# power.net
KiCad netlist of a schematic drawn in Altium Designer
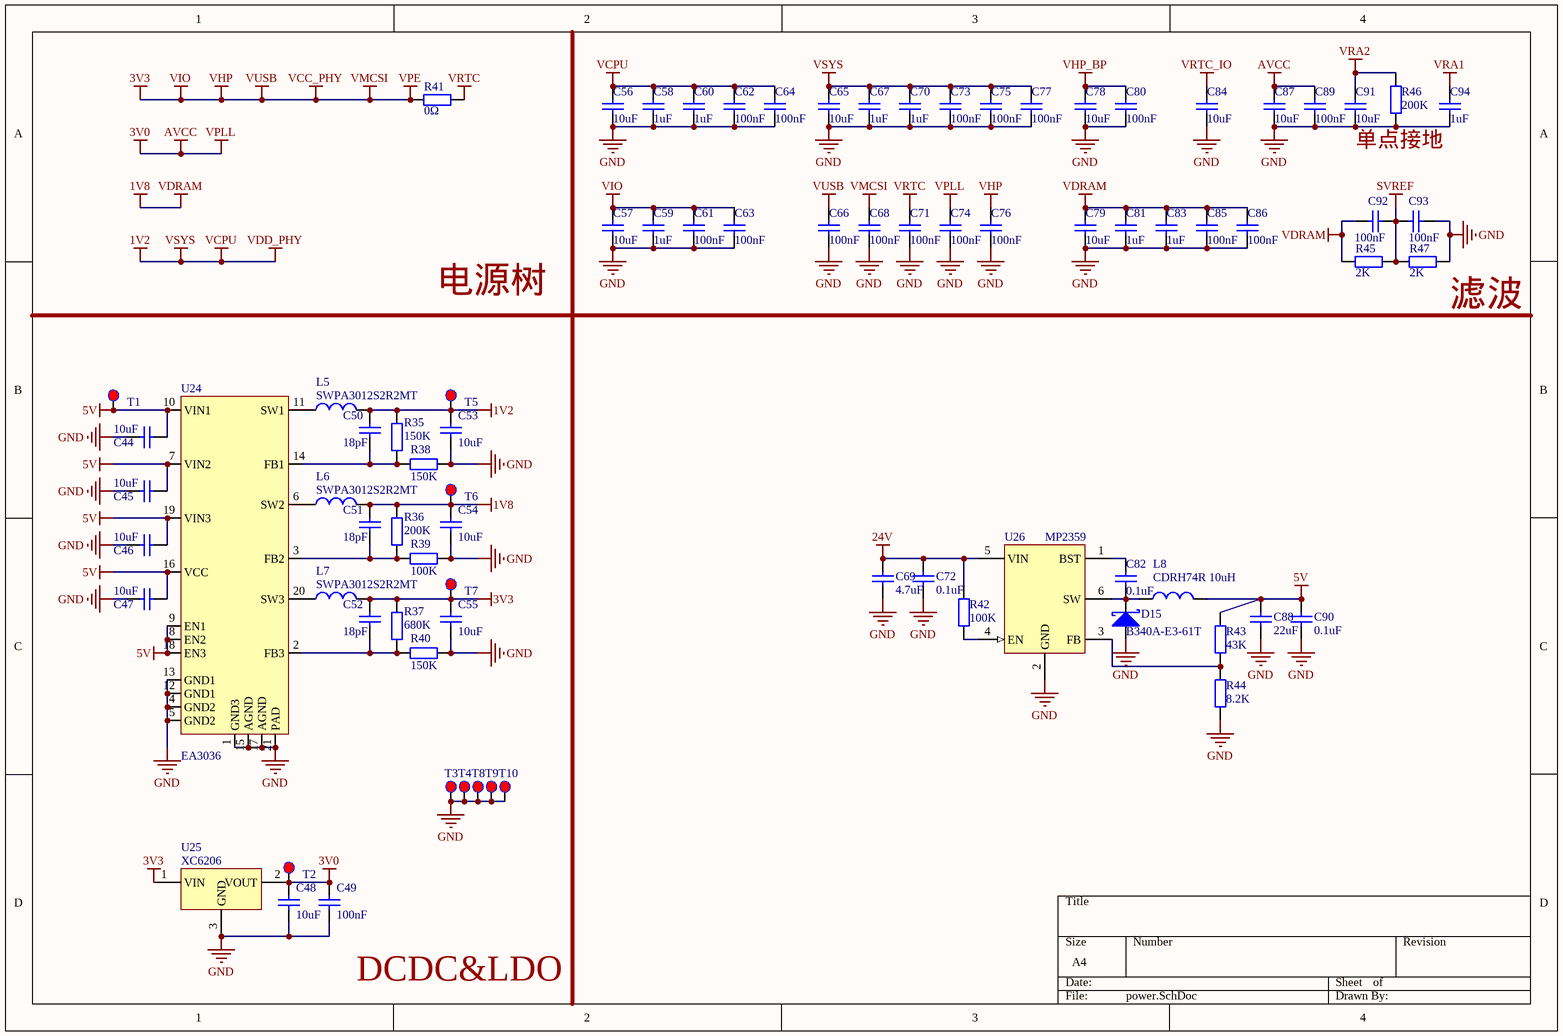
[diagram p0: power.SchDoc]

(export (version "E")
  (design (tool "Eeschema 10.0.6"))
  (components
    (comp (ref "C44")
      (value "10uF")
      (footprint "CAPC1608L")
      (description "Capacitor")
      (fields (field (name "PUBLISHER") "Altium Limited"))
      (libsource (lib "Peace的集成库") (part "Cap1"))
    )
    (comp (ref "C45")
      (value "10uF")
      (footprint "CAPC1608L")
      (description "Capacitor")
      (fields (field (name "PUBLISHER") "Altium Limited"))
      (libsource (lib "Peace的集成库") (part "Cap1"))
    )
    (comp (ref "C46")
      (value "10uF")
      (footprint "CAPC1608L")
      (description "Capacitor")
      (fields (field (name "PUBLISHER") "Altium Limited"))
      (libsource (lib "Peace的集成库") (part "Cap1"))
    )
    (comp (ref "C47")
      (value "10uF")
      (footprint "CAPC1608L")
      (description "Capacitor")
      (fields (field (name "PUBLISHER") "Altium Limited"))
      (libsource (lib "Peace的集成库") (part "Cap1"))
    )
    (comp (ref "C48")
      (value "10uF")
      (footprint "CAPC1608L")
      (description "Capacitor")
      (fields (field (name "PUBLISHER") "Altium Limited"))
      (libsource (lib "Peace的集成库") (part "Cap1"))
    )
    (comp (ref "C49")
      (value "100nF")
      (footprint "CAPC1608L")
      (description "Capacitor")
      (fields (field (name "PUBLISHER") "Altium Limited"))
      (libsource (lib "Peace的集成库") (part "Cap1"))
    )
    (comp (ref "C50")
      (value "18pF")
      (footprint "CAPC1608L")
      (description "Capacitor")
      (fields (field (name "PUBLISHER") "Altium Limited"))
      (libsource (lib "Peace的集成库") (part "Cap1"))
    )
    (comp (ref "C51")
      (value "18pF")
      (footprint "CAPC1608L")
      (description "Capacitor")
      (fields (field (name "PUBLISHER") "Altium Limited"))
      (libsource (lib "Peace的集成库") (part "Cap1"))
    )
    (comp (ref "C52")
      (value "18pF")
      (footprint "CAPC1608L")
      (description "Capacitor")
      (fields (field (name "PUBLISHER") "Altium Limited"))
      (libsource (lib "Peace的集成库") (part "Cap1"))
    )
    (comp (ref "C53")
      (value "10uF")
      (footprint "CAPC1608L")
      (description "Capacitor")
      (fields (field (name "PUBLISHER") "Altium Limited"))
      (libsource (lib "Peace的集成库") (part "Cap1"))
    )
    (comp (ref "C54")
      (value "10uF")
      (footprint "CAPC1608L")
      (description "Capacitor")
      (fields (field (name "PUBLISHER") "Altium Limited"))
      (libsource (lib "Peace的集成库") (part "Cap1"))
    )
    (comp (ref "C55")
      (value "10uF")
      (footprint "CAPC1608L")
      (description "Capacitor")
      (fields (field (name "PUBLISHER") "Altium Limited"))
      (libsource (lib "Peace的集成库") (part "Cap1"))
    )
    (comp (ref "C56")
      (value "10uF")
      (footprint "CAPC1608L")
      (description "Capacitor")
      (fields (field (name "PUBLISHER") "Altium Limited"))
      (libsource (lib "Peace的集成库") (part "Cap1"))
    )
    (comp (ref "C57")
      (value "10uF")
      (footprint "CAPC1608L")
      (description "Capacitor")
      (fields (field (name "PUBLISHER") "Altium Limited"))
      (libsource (lib "Peace的集成库") (part "Cap1"))
    )
    (comp (ref "C58")
      (value "1uF")
      (footprint "CAPC1608L")
      (description "Capacitor")
      (fields (field (name "PUBLISHER") "Altium Limited"))
      (libsource (lib "Peace的集成库") (part "Cap1"))
    )
    (comp (ref "C59")
      (value "1uF")
      (footprint "CAPC1608L")
      (description "Capacitor")
      (fields (field (name "PUBLISHER") "Altium Limited"))
      (libsource (lib "Peace的集成库") (part "Cap1"))
    )
    (comp (ref "C60")
      (value "1uF")
      (footprint "CAPC1608L")
      (description "Capacitor")
      (fields (field (name "PUBLISHER") "Altium Limited"))
      (libsource (lib "Peace的集成库") (part "Cap1"))
    )
    (comp (ref "C61")
      (value "100nF")
      (footprint "CAPC1608L")
      (description "Capacitor")
      (fields (field (name "PUBLISHER") "Altium Limited"))
      (libsource (lib "Peace的集成库") (part "Cap1"))
    )
    (comp (ref "C62")
      (value "100nF")
      (footprint "CAPC1608L")
      (description "Capacitor")
      (fields (field (name "PUBLISHER") "Altium Limited"))
      (libsource (lib "Peace的集成库") (part "Cap1"))
    )
    (comp (ref "C63")
      (value "100nF")
      (footprint "CAPC1608L")
      (description "Capacitor")
      (fields (field (name "PUBLISHER") "Altium Limited"))
      (libsource (lib "Peace的集成库") (part "Cap1"))
    )
    (comp (ref "C64")
      (value "100nF")
      (footprint "CAPC1608L")
      (description "Capacitor")
      (fields (field (name "PUBLISHER") "Altium Limited"))
      (libsource (lib "Peace的集成库") (part "Cap1"))
    )
    (comp (ref "C65")
      (value "10uF")
      (footprint "CAPC1608L")
      (description "Capacitor")
      (fields (field (name "PUBLISHER") "Altium Limited"))
      (libsource (lib "Peace的集成库") (part "Cap1"))
    )
    (comp (ref "C66")
      (value "100nF")
      (footprint "CAPC1608L")
      (description "Capacitor")
      (fields (field (name "PUBLISHER") "Altium Limited"))
      (libsource (lib "Peace的集成库") (part "Cap1"))
    )
    (comp (ref "C67")
      (value "1uF")
      (footprint "CAPC1608L")
      (description "Capacitor")
      (fields (field (name "PUBLISHER") "Altium Limited"))
      (libsource (lib "Peace的集成库") (part "Cap1"))
    )
    (comp (ref "C68")
      (value "100nF")
      (footprint "CAPC1608L")
      (description "Capacitor")
      (fields (field (name "PUBLISHER") "Altium Limited"))
      (libsource (lib "Peace的集成库") (part "Cap1"))
    )
    (comp (ref "C69")
      (value "4.7uF")
      (footprint "CAPC3216L")
      (description "Capacitor")
      (fields (field (name "PUBLISHER") "Altium Limited"))
      (libsource (lib "Peace的集成库") (part "Cap1"))
    )
    (comp (ref "C70")
      (value "1uF")
      (footprint "CAPC1608L")
      (description "Capacitor")
      (fields (field (name "PUBLISHER") "Altium Limited"))
      (libsource (lib "Peace的集成库") (part "Cap1"))
    )
    (comp (ref "C71")
      (value "100nF")
      (footprint "CAPC1608L")
      (description "Capacitor")
      (fields (field (name "PUBLISHER") "Altium Limited"))
      (libsource (lib "Peace的集成库") (part "Cap1"))
    )
    (comp (ref "C72")
      (value "0.1uF")
      (footprint "CAPC2012L")
      (description "Capacitor")
      (fields (field (name "PUBLISHER") "Altium Limited"))
      (libsource (lib "Peace的集成库") (part "Cap1"))
    )
    (comp (ref "C73")
      (value "100nF")
      (footprint "CAPC1608L")
      (description "Capacitor")
      (fields (field (name "PUBLISHER") "Altium Limited"))
      (libsource (lib "Peace的集成库") (part "Cap1"))
    )
    (comp (ref "C74")
      (value "100nF")
      (footprint "CAPC1608L")
      (description "Capacitor")
      (fields (field (name "PUBLISHER") "Altium Limited"))
      (libsource (lib "Peace的集成库") (part "Cap1"))
    )
    (comp (ref "C75")
      (value "100nF")
      (footprint "CAPC1608L")
      (description "Capacitor")
      (fields (field (name "PUBLISHER") "Altium Limited"))
      (libsource (lib "Peace的集成库") (part "Cap1"))
    )
    (comp (ref "C76")
      (value "100nF")
      (footprint "CAPC1608L")
      (description "Capacitor")
      (fields (field (name "PUBLISHER") "Altium Limited"))
      (libsource (lib "Peace的集成库") (part "Cap1"))
    )
    (comp (ref "C77")
      (value "100nF")
      (footprint "CAPC1608L")
      (description "Capacitor")
      (fields (field (name "PUBLISHER") "Altium Limited"))
      (libsource (lib "Peace的集成库") (part "Cap1"))
    )
    (comp (ref "C78")
      (value "10uF")
      (footprint "CAPC1608L")
      (description "Capacitor")
      (fields (field (name "PUBLISHER") "Altium Limited"))
      (libsource (lib "Peace的集成库") (part "Cap1"))
    )
    (comp (ref "C79")
      (value "10uF")
      (footprint "CAPC1608L")
      (description "Capacitor")
      (fields (field (name "PUBLISHER") "Altium Limited"))
      (libsource (lib "Peace的集成库") (part "Cap1"))
    )
    (comp (ref "C80")
      (value "100nF")
      (footprint "CAPC1608L")
      (description "Capacitor")
      (fields (field (name "PUBLISHER") "Altium Limited"))
      (libsource (lib "Peace的集成库") (part "Cap1"))
    )
    (comp (ref "C81")
      (value "1uF")
      (footprint "CAPC1608L")
      (description "Capacitor")
      (fields (field (name "PUBLISHER") "Altium Limited"))
      (libsource (lib "Peace的集成库") (part "Cap1"))
    )
    (comp (ref "C82")
      (value "0.1uF")
      (footprint "CAPC1608L")
      (description "Capacitor")
      (fields (field (name "PUBLISHER") "Altium Limited"))
      (libsource (lib "Peace的集成库") (part "Cap1"))
    )
    (comp (ref "C83")
      (value "1uF")
      (footprint "CAPC1608L")
      (description "Capacitor")
      (fields (field (name "PUBLISHER") "Altium Limited"))
      (libsource (lib "Peace的集成库") (part "Cap1"))
    )
    (comp (ref "C84")
      (value "10uF")
      (footprint "CAPC1608L")
      (description "Capacitor")
      (fields (field (name "PUBLISHER") "Altium Limited"))
      (libsource (lib "Peace的集成库") (part "Cap1"))
    )
    (comp (ref "C85")
      (value "100nF")
      (footprint "CAPC1608L")
      (description "Capacitor")
      (fields (field (name "PUBLISHER") "Altium Limited"))
      (libsource (lib "Peace的集成库") (part "Cap1"))
    )
    (comp (ref "C86")
      (value "100nF")
      (footprint "CAPC1608L")
      (description "Capacitor")
      (fields (field (name "PUBLISHER") "Altium Limited"))
      (libsource (lib "Peace的集成库") (part "Cap1"))
    )
    (comp (ref "C87")
      (value "10uF")
      (footprint "CAPC1608L")
      (description "Capacitor")
      (fields (field (name "PUBLISHER") "Altium Limited"))
      (libsource (lib "Peace的集成库") (part "Cap1"))
    )
    (comp (ref "C88")
      (value "22uF")
      (footprint "CAPC3216L")
      (description "Capacitor")
      (fields (field (name "PUBLISHER") "Altium Limited"))
      (libsource (lib "Peace的集成库") (part "Cap1"))
    )
    (comp (ref "C89")
      (value "100nF")
      (footprint "CAPC1608L")
      (description "Capacitor")
      (fields (field (name "PUBLISHER") "Altium Limited"))
      (libsource (lib "Peace的集成库") (part "Cap1"))
    )
    (comp (ref "C90")
      (value "0.1uF")
      (footprint "CAPC2012L")
      (description "Capacitor")
      (fields (field (name "PUBLISHER") "Altium Limited"))
      (libsource (lib "Peace的集成库") (part "Cap1"))
    )
    (comp (ref "C91")
      (value "10uF")
      (footprint "CAPC1608L")
      (description "Capacitor")
      (fields (field (name "PUBLISHER") "Altium Limited"))
      (libsource (lib "Peace的集成库") (part "Cap1"))
    )
    (comp (ref "C92")
      (value "100nF")
      (footprint "CAPC1608L")
      (description "Capacitor")
      (fields (field (name "PUBLISHER") "Altium Limited"))
      (libsource (lib "Peace的集成库") (part "Cap1"))
    )
    (comp (ref "C93")
      (value "100nF")
      (footprint "CAPC1608L")
      (description "Capacitor")
      (fields (field (name "PUBLISHER") "Altium Limited"))
      (libsource (lib "Peace的集成库") (part "Cap1"))
    )
    (comp (ref "C94")
      (value "1uF")
      (footprint "CAPC1608L")
      (description "Capacitor")
      (fields (field (name "PUBLISHER") "Altium Limited"))
      (libsource (lib "Peace的集成库") (part "Cap1"))
    )
    (comp (ref "D15")
      (value "B340A-E3-61T")
      (footprint "DO-214AC")
      (description "Schottky Diode")
      (fields (field (name "PUBLISHER") "Altium Limited"))
      (libsource (lib "原理图库") (part "D Schottky"))
    )
    (comp (ref "L5")
      (value "SWPA3012S2R2MT")
      (footprint "IND3012_L")
      (description "Inductor")
      (fields (field (name "PUBLISHER") "Altium Limited"))
      (libsource (lib "Peace的集成库") (part "Inductor"))
    )
    (comp (ref "L6")
      (value "SWPA3012S2R2MT")
      (footprint "IND3012_L")
      (description "Inductor")
      (fields (field (name "PUBLISHER") "Altium Limited"))
      (libsource (lib "Peace的集成库") (part "Inductor"))
    )
    (comp (ref "L7")
      (value "SWPA3012S2R2MT")
      (footprint "IND3012_L")
      (description "Inductor")
      (fields (field (name "PUBLISHER") "Altium Limited"))
      (libsource (lib "Peace的集成库") (part "Inductor"))
    )
    (comp (ref "L8")
      (value "CDRH74R 10uH")
      (footprint "IND_7545")
      (description "Inductor")
      (fields (field (name "PUBLISHER") "Altium Limited"))
      (libsource (lib "原理图库") (part "Inductor"))
    )
    (comp (ref "R35")
      (value "150K")
      (footprint "RESC1608L")
      (description "Resistor")
      (fields (field (name "PUBLISHER") "Altium Limited"))
      (libsource (lib "Peace的集成库") (part "Res1"))
    )
    (comp (ref "R36")
      (value "200K")
      (footprint "RESC1608L")
      (description "Resistor")
      (fields (field (name "PUBLISHER") "Altium Limited"))
      (libsource (lib "Peace的集成库") (part "Res1"))
    )
    (comp (ref "R37")
      (value "680K")
      (footprint "RESC1608L")
      (description "Resistor")
      (fields (field (name "PUBLISHER") "Altium Limited"))
      (libsource (lib "Peace的集成库") (part "Res1"))
    )
    (comp (ref "R38")
      (value "150K")
      (footprint "RESC1608L")
      (description "Resistor")
      (fields (field (name "PUBLISHER") "Altium Limited"))
      (libsource (lib "") (part "Res1_1"))
    )
    (comp (ref "R39")
      (value "100K")
      (footprint "RESC1608L")
      (description "Resistor")
      (fields (field (name "PUBLISHER") "Altium Limited"))
      (libsource (lib "") (part "Res1_1"))
    )
    (comp (ref "R40")
      (value "150K")
      (footprint "RESC1608L")
      (description "Resistor")
      (fields (field (name "PUBLISHER") "Altium Limited"))
      (libsource (lib "") (part "Res1_1"))
    )
    (comp (ref "R41")
      (value "0Ω")
      (footprint "RESC1608L")
      (description "Resistor")
      (fields (field (name "PUBLISHER") "Altium Limited"))
      (libsource (lib "") (part "Res1_2"))
    )
    (comp (ref "R42")
      (value "100K")
      (footprint "RESC1608L")
      (description "Resistor")
      (fields (field (name "PUBLISHER") "Altium Limited"))
      (libsource (lib "Peace的集成库") (part "Res1"))
    )
    (comp (ref "R43")
      (value "43K")
      (footprint "RESC1608L")
      (description "Resistor")
      (fields (field (name "PUBLISHER") "Altium Limited"))
      (libsource (lib "Peace的集成库") (part "Res1"))
    )
    (comp (ref "R44")
      (value "8.2K")
      (footprint "RESC1608L")
      (description "Resistor")
      (fields (field (name "PUBLISHER") "Altium Limited"))
      (libsource (lib "Peace的集成库") (part "Res1"))
    )
    (comp (ref "R45")
      (value "2K")
      (footprint "RESC1608L")
      (description "Resistor")
      (fields (field (name "PUBLISHER") "Altium Limited"))
      (libsource (lib "") (part "Res1_2"))
    )
    (comp (ref "R46")
      (value "200K")
      (footprint "RESC1608L")
      (description "Resistor")
      (fields (field (name "PUBLISHER") "Altium Limited"))
      (libsource (lib "Peace的集成库") (part "Res1"))
    )
    (comp (ref "R47")
      (value "2K")
      (footprint "RESC1608L")
      (description "Resistor")
      (fields (field (name "PUBLISHER") "Altium Limited"))
      (libsource (lib "") (part "Res1_2"))
    )
    (comp (ref "T1")
      (value "TEST_POINT")
      (footprint "TEST_POINT_0.8")
      (description "测试点")
      (libsource (lib "Peace的集成库") (part "TEST_POINT"))
    )
    (comp (ref "T2")
      (value "TEST_POINT")
      (footprint "TEST_POINT_0.8")
      (description "测试点")
      (libsource (lib "Peace的集成库") (part "TEST_POINT"))
    )
    (comp (ref "T3")
      (value "TEST_POINT")
      (footprint "TEST_POINT_0.8")
      (description "测试点")
      (libsource (lib "Peace的集成库") (part "TEST_POINT"))
    )
    (comp (ref "T4")
      (value "TEST_POINT")
      (footprint "TEST_POINT_0.8")
      (description "测试点")
      (libsource (lib "Peace的集成库") (part "TEST_POINT"))
    )
    (comp (ref "T5")
      (value "TEST_POINT")
      (footprint "TEST_POINT_0.8")
      (description "测试点")
      (libsource (lib "Peace的集成库") (part "TEST_POINT"))
    )
    (comp (ref "T6")
      (value "TEST_POINT")
      (footprint "TEST_POINT_0.8")
      (description "测试点")
      (libsource (lib "Peace的集成库") (part "TEST_POINT"))
    )
    (comp (ref "T7")
      (value "TEST_POINT")
      (footprint "TEST_POINT_0.8")
      (description "测试点")
      (libsource (lib "Peace的集成库") (part "TEST_POINT"))
    )
    (comp (ref "T8")
      (value "TEST_POINT")
      (footprint "TEST_POINT_0.8")
      (description "测试点")
      (libsource (lib "Peace的集成库") (part "TEST_POINT"))
    )
    (comp (ref "T9")
      (value "TEST_POINT")
      (footprint "TEST_POINT_0.8")
      (description "测试点")
      (libsource (lib "Peace的集成库") (part "TEST_POINT"))
    )
    (comp (ref "T10")
      (value "TEST_POINT")
      (footprint "TEST_POINT_0.8")
      (description "测试点")
      (libsource (lib "Peace的集成库") (part "TEST_POINT"))
    )
    (comp (ref "U24") (value "EA3036") (footprint "QFN20_L") (libsource (lib "原理图库") (part "EA3036")))
    (comp (ref "U25")
      (value "XC6206")
      (footprint "SOT23_L")
      (libsource (lib "Peace的集成库") (part "LDO-SOT23-3"))
    )
    (comp (ref "U26")
      (value "MP2359")
      (footprint "SOT23-6_L")
      (description "1.2A, 24V, 1.4MHz异步降压转换器")
      (libsource (lib "Peace的集成库") (part "MP2359"))
    )
  )
  (nets
    (net (code "1") (name "1V2") (class "Default")
      (node (ref "C50") (pin "2") (pinfunction "2_2") (pintype "passive"))
      (node (ref "C53") (pin "2") (pinfunction "2_2") (pintype "passive"))
      (node (ref "C56") (pin "2") (pinfunction "2_2") (pintype "passive"))
      (node (ref "C58") (pin "2") (pinfunction "2_2") (pintype "passive"))
      (node (ref "C60") (pin "2") (pinfunction "2_2") (pintype "passive"))
      (node (ref "C62") (pin "2") (pinfunction "2_2") (pintype "passive"))
      (node (ref "C64") (pin "2") (pinfunction "2_2") (pintype "passive"))
      (node (ref "C65") (pin "2") (pinfunction "2_2") (pintype "passive"))
      (node (ref "C67") (pin "2") (pinfunction "2_2") (pintype "passive"))
      (node (ref "C70") (pin "2") (pinfunction "2_2") (pintype "passive"))
      (node (ref "C73") (pin "2") (pinfunction "2_2") (pintype "passive"))
      (node (ref "C75") (pin "2") (pinfunction "2_2") (pintype "passive"))
      (node (ref "C77") (pin "2") (pinfunction "2_2") (pintype "passive"))
      (node (ref "L5") (pin "2") (pinfunction "2_2") (pintype "passive"))
      (node (ref "R35") (pin "2") (pinfunction "2_2") (pintype "passive"))
      (node (ref "T5") (pin "1") (pintype "passive"))
    )
    (net (code "2") (name "1V8") (class "Default")
      (node (ref "C51") (pin "2") (pinfunction "2_2") (pintype "passive"))
      (node (ref "C54") (pin "2") (pinfunction "2_2") (pintype "passive"))
      (node (ref "C79") (pin "2") (pinfunction "2_2") (pintype "passive"))
      (node (ref "C81") (pin "2") (pinfunction "2_2") (pintype "passive"))
      (node (ref "C83") (pin "2") (pinfunction "2_2") (pintype "passive"))
      (node (ref "C85") (pin "2") (pinfunction "2_2") (pintype "passive"))
      (node (ref "C86") (pin "2") (pinfunction "2_2") (pintype "passive"))
      (node (ref "C92") (pin "2") (pinfunction "2_2") (pintype "passive"))
      (node (ref "L6") (pin "2") (pinfunction "2_2") (pintype "passive"))
      (node (ref "R36") (pin "2") (pinfunction "2_2") (pintype "passive"))
      (node (ref "R45") (pin "1") (pinfunction "1_1") (pintype "passive"))
      (node (ref "T6") (pin "1") (pintype "passive"))
    )
    (net (code "3") (name "3V0") (class "Default")
      (node (ref "C48") (pin "2") (pinfunction "2_2") (pintype "passive"))
      (node (ref "C49") (pin "2") (pinfunction "2_2") (pintype "passive"))
      (node (ref "C74") (pin "2") (pinfunction "2_2") (pintype "passive"))
      (node (ref "C87") (pin "2") (pinfunction "2_2") (pintype "passive"))
      (node (ref "C89") (pin "2") (pinfunction "2_2") (pintype "passive"))
      (node (ref "T2") (pin "1") (pintype "passive"))
      (node (ref "U25") (pin "2") (pinfunction "VOUT_2") (pintype "passive"))
    )
    (net (code "4") (name "3V3") (class "Default")
      (node (ref "C52") (pin "2") (pinfunction "2_2") (pintype "passive"))
      (node (ref "C55") (pin "2") (pinfunction "2_2") (pintype "passive"))
      (node (ref "C57") (pin "2") (pinfunction "2_2") (pintype "passive"))
      (node (ref "C59") (pin "2") (pinfunction "2_2") (pintype "passive"))
      (node (ref "C61") (pin "2") (pinfunction "2_2") (pintype "passive"))
      (node (ref "C63") (pin "2") (pinfunction "2_2") (pintype "passive"))
      (node (ref "C66") (pin "2") (pinfunction "2_2") (pintype "passive"))
      (node (ref "C68") (pin "2") (pinfunction "2_2") (pintype "passive"))
      (node (ref "C76") (pin "2") (pinfunction "2_2") (pintype "passive"))
      (node (ref "L7") (pin "2") (pinfunction "2_2") (pintype "passive"))
      (node (ref "R37") (pin "2") (pinfunction "2_2") (pintype "passive"))
      (node (ref "R41") (pin "1") (pinfunction "1_1") (pintype "passive"))
      (node (ref "T7") (pin "1") (pintype "passive"))
      (node (ref "U25") (pin "1") (pinfunction "VIN_1") (pintype "passive"))
    )
    (net (code "5") (name "5V") (class "Default")
      (node (ref "C44") (pin "1") (pinfunction "1_1") (pintype "passive"))
      (node (ref "C45") (pin "1") (pinfunction "1_1") (pintype "passive"))
      (node (ref "C46") (pin "1") (pinfunction "1_1") (pintype "passive"))
      (node (ref "C47") (pin "1") (pinfunction "1_1") (pintype "passive"))
      (node (ref "C88") (pin "2") (pinfunction "2_2") (pintype "passive"))
      (node (ref "C90") (pin "2") (pinfunction "2_2") (pintype "passive"))
      (node (ref "L8") (pin "2") (pinfunction "2_2") (pintype "passive"))
      (node (ref "R43") (pin "2") (pinfunction "2_2") (pintype "passive"))
      (node (ref "T1") (pin "1") (pintype "passive"))
      (node (ref "U24") (pin "10") (pinfunction "VIN1_10") (pintype "passive"))
      (node (ref "U24") (pin "16") (pinfunction "VCC_16") (pintype "passive"))
      (node (ref "U24") (pin "18") (pinfunction "EN3_18") (pintype "passive"))
      (node (ref "U24") (pin "19") (pinfunction "VIN3_19") (pintype "passive"))
      (node (ref "U24") (pin "7") (pinfunction "VIN2_7") (pintype "passive"))
      (node (ref "U24") (pin "8") (pinfunction "EN2_8") (pintype "passive"))
      (node (ref "U24") (pin "9") (pinfunction "EN1_9") (pintype "passive"))
    )
    (net (code "6") (name "24V") (class "Default")
      (node (ref "C69") (pin "2") (pinfunction "2_2") (pintype "passive"))
      (node (ref "C72") (pin "2") (pinfunction "2_2") (pintype "passive"))
      (node (ref "R42") (pin "2") (pinfunction "2_2") (pintype "passive"))
      (node (ref "U26") (pin "5") (pinfunction "VIN_5") (pintype "power_in"))
    )
    (net (code "7") (name "GND") (class "Default")
      (node (ref "C44") (pin "2") (pinfunction "2_2") (pintype "passive"))
      (node (ref "C45") (pin "2") (pinfunction "2_2") (pintype "passive"))
      (node (ref "C46") (pin "2") (pinfunction "2_2") (pintype "passive"))
      (node (ref "C47") (pin "2") (pinfunction "2_2") (pintype "passive"))
      (node (ref "C48") (pin "1") (pinfunction "1_1") (pintype "passive"))
      (node (ref "C49") (pin "1") (pinfunction "1_1") (pintype "passive"))
      (node (ref "C53") (pin "1") (pinfunction "1_1") (pintype "passive"))
      (node (ref "C54") (pin "1") (pinfunction "1_1") (pintype "passive"))
      (node (ref "C55") (pin "1") (pinfunction "1_1") (pintype "passive"))
      (node (ref "C56") (pin "1") (pinfunction "1_1") (pintype "passive"))
      (node (ref "C57") (pin "1") (pinfunction "1_1") (pintype "passive"))
      (node (ref "C58") (pin "1") (pinfunction "1_1") (pintype "passive"))
      (node (ref "C59") (pin "1") (pinfunction "1_1") (pintype "passive"))
      (node (ref "C60") (pin "1") (pinfunction "1_1") (pintype "passive"))
      (node (ref "C61") (pin "1") (pinfunction "1_1") (pintype "passive"))
      (node (ref "C62") (pin "1") (pinfunction "1_1") (pintype "passive"))
      (node (ref "C63") (pin "1") (pinfunction "1_1") (pintype "passive"))
      (node (ref "C64") (pin "1") (pinfunction "1_1") (pintype "passive"))
      (node (ref "C65") (pin "1") (pinfunction "1_1") (pintype "passive"))
      (node (ref "C66") (pin "1") (pinfunction "1_1") (pintype "passive"))
      (node (ref "C67") (pin "1") (pinfunction "1_1") (pintype "passive"))
      (node (ref "C68") (pin "1") (pinfunction "1_1") (pintype "passive"))
      (node (ref "C69") (pin "1") (pinfunction "1_1") (pintype "passive"))
      (node (ref "C70") (pin "1") (pinfunction "1_1") (pintype "passive"))
      (node (ref "C71") (pin "1") (pinfunction "1_1") (pintype "passive"))
      (node (ref "C72") (pin "1") (pinfunction "1_1") (pintype "passive"))
      (node (ref "C73") (pin "1") (pinfunction "1_1") (pintype "passive"))
      (node (ref "C74") (pin "1") (pinfunction "1_1") (pintype "passive"))
      (node (ref "C75") (pin "1") (pinfunction "1_1") (pintype "passive"))
      (node (ref "C76") (pin "1") (pinfunction "1_1") (pintype "passive"))
      (node (ref "C77") (pin "1") (pinfunction "1_1") (pintype "passive"))
      (node (ref "C78") (pin "1") (pinfunction "1_1") (pintype "passive"))
      (node (ref "C79") (pin "1") (pinfunction "1_1") (pintype "passive"))
      (node (ref "C80") (pin "1") (pinfunction "1_1") (pintype "passive"))
      (node (ref "C81") (pin "1") (pinfunction "1_1") (pintype "passive"))
      (node (ref "C83") (pin "1") (pinfunction "1_1") (pintype "passive"))
      (node (ref "C84") (pin "1") (pinfunction "1_1") (pintype "passive"))
      (node (ref "C85") (pin "1") (pinfunction "1_1") (pintype "passive"))
      (node (ref "C86") (pin "1") (pinfunction "1_1") (pintype "passive"))
      (node (ref "C87") (pin "1") (pinfunction "1_1") (pintype "passive"))
      (node (ref "C88") (pin "1") (pinfunction "1_1") (pintype "passive"))
      (node (ref "C89") (pin "1") (pinfunction "1_1") (pintype "passive"))
      (node (ref "C90") (pin "1") (pinfunction "1_1") (pintype "passive"))
      (node (ref "C91") (pin "1") (pinfunction "1_1") (pintype "passive"))
      (node (ref "C93") (pin "1") (pinfunction "1_1") (pintype "passive"))
      (node (ref "C94") (pin "1") (pinfunction "1_1") (pintype "passive"))
      (node (ref "D15") (pin "1") (pinfunction "A_1") (pintype "passive"))
      (node (ref "R38") (pin "1") (pinfunction "1_1") (pintype "passive"))
      (node (ref "R39") (pin "1") (pinfunction "1_1") (pintype "passive"))
      (node (ref "R40") (pin "1") (pinfunction "1_1") (pintype "passive"))
      (node (ref "R44") (pin "1") (pinfunction "1_1") (pintype "passive"))
      (node (ref "R46") (pin "1") (pinfunction "1_1") (pintype "passive"))
      (node (ref "R47") (pin "2") (pinfunction "2_2") (pintype "passive"))
      (node (ref "T10") (pin "1") (pintype "passive"))
      (node (ref "T3") (pin "1") (pintype "passive"))
      (node (ref "T4") (pin "1") (pintype "passive"))
      (node (ref "T8") (pin "1") (pintype "passive"))
      (node (ref "T9") (pin "1") (pintype "passive"))
      (node (ref "U24") (pin "1") (pinfunction "GND3_1") (pintype "passive"))
      (node (ref "U24") (pin "12") (pinfunction "GND1_12") (pintype "passive"))
      (node (ref "U24") (pin "13") (pinfunction "GND1_13") (pintype "passive"))
      (node (ref "U24") (pin "15") (pinfunction "AGND_15") (pintype "passive"))
      (node (ref "U24") (pin "17") (pinfunction "AGND_17") (pintype "passive"))
      (node (ref "U24") (pin "21") (pinfunction "PAD_21") (pintype "passive"))
      (node (ref "U24") (pin "4") (pinfunction "GND2_4") (pintype "passive"))
      (node (ref "U24") (pin "5") (pinfunction "GND2_5") (pintype "passive"))
      (node (ref "U25") (pin "3") (pinfunction "GND_3") (pintype "passive"))
      (node (ref "U26") (pin "2") (pinfunction "GND_2") (pintype "power_in"))
    )
    (net (code "8") (name "Net-(D15-K)") (class "Default")
      (node (ref "C82") (pin "1") (pinfunction "1_1") (pintype "passive"))
      (node (ref "D15") (pin "2") (pinfunction "K_2") (pintype "passive"))
      (node (ref "L8") (pin "1") (pinfunction "1_1") (pintype "passive"))
      (node (ref "U26") (pin "6") (pinfunction "SW_6") (pintype "passive"))
    )
    (net (code "9") (name "Net-(U24-FB1)") (class "Default")
      (node (ref "C50") (pin "1") (pinfunction "1_1") (pintype "passive"))
      (node (ref "R35") (pin "1") (pinfunction "1_1") (pintype "passive"))
      (node (ref "R38") (pin "2") (pinfunction "2_2") (pintype "passive"))
      (node (ref "U24") (pin "14") (pinfunction "FB1_14") (pintype "passive"))
    )
    (net (code "10") (name "Net-(U24-FB2)") (class "Default")
      (node (ref "C51") (pin "1") (pinfunction "1_1") (pintype "passive"))
      (node (ref "R36") (pin "1") (pinfunction "1_1") (pintype "passive"))
      (node (ref "R39") (pin "2") (pinfunction "2_2") (pintype "passive"))
      (node (ref "U24") (pin "3") (pinfunction "FB2_3") (pintype "passive"))
    )
    (net (code "11") (name "Net-(U24-FB3)") (class "Default")
      (node (ref "C52") (pin "1") (pinfunction "1_1") (pintype "passive"))
      (node (ref "R37") (pin "1") (pinfunction "1_1") (pintype "passive"))
      (node (ref "R40") (pin "2") (pinfunction "2_2") (pintype "passive"))
      (node (ref "U24") (pin "2") (pinfunction "FB3_2") (pintype "passive"))
    )
    (net (code "12") (name "Net-(U24-SW1)") (class "Default")
      (node (ref "L5") (pin "1") (pinfunction "1_1") (pintype "passive"))
      (node (ref "U24") (pin "11") (pinfunction "SW1_11") (pintype "passive"))
    )
    (net (code "13") (name "Net-(U24-SW2)") (class "Default")
      (node (ref "L6") (pin "1") (pinfunction "1_1") (pintype "passive"))
      (node (ref "U24") (pin "6") (pinfunction "SW2_6") (pintype "passive"))
    )
    (net (code "14") (name "Net-(U24-SW3)") (class "Default")
      (node (ref "L7") (pin "1") (pinfunction "1_1") (pintype "passive"))
      (node (ref "U24") (pin "20") (pinfunction "SW3_20") (pintype "passive"))
    )
    (net (code "15") (name "Net-(U26-BST)") (class "Default")
      (node (ref "C82") (pin "2") (pinfunction "2_2") (pintype "passive"))
      (node (ref "U26") (pin "1") (pinfunction "BST_1") (pintype "passive"))
    )
    (net (code "16") (name "Net-(U26-EN)") (class "Default")
      (node (ref "R42") (pin "1") (pinfunction "1_1") (pintype "passive"))
      (node (ref "U26") (pin "4") (pinfunction "EN_4") (pintype "input"))
    )
    (net (code "17") (name "Net-(U26-FB)") (class "Default")
      (node (ref "R43") (pin "1") (pinfunction "1_1") (pintype "passive"))
      (node (ref "R44") (pin "2") (pinfunction "2_2") (pintype "passive"))
      (node (ref "U26") (pin "3") (pinfunction "FB_3") (pintype "passive"))
    )
    (net (code "18") (name "SVREF") (class "Default")
      (node (ref "C92") (pin "1") (pinfunction "1_1") (pintype "passive"))
      (node (ref "C93") (pin "2") (pinfunction "2_2") (pintype "passive"))
      (node (ref "R45") (pin "2") (pinfunction "2_2") (pintype "passive"))
      (node (ref "R47") (pin "1") (pinfunction "1_1") (pintype "passive"))
    )
    (net (code "19") (name "VHP_BP") (class "Default")
      (node (ref "C78") (pin "2") (pinfunction "2_2") (pintype "passive"))
      (node (ref "C80") (pin "2") (pinfunction "2_2") (pintype "passive"))
    )
    (net (code "20") (name "VRA1") (class "Default")
      (node (ref "C94") (pin "2") (pinfunction "2_2") (pintype "passive"))
    )
    (net (code "21") (name "VRA2") (class "Default")
      (node (ref "C91") (pin "2") (pinfunction "2_2") (pintype "passive"))
      (node (ref "R46") (pin "2") (pinfunction "2_2") (pintype "passive"))
    )
    (net (code "22") (name "VRTC") (class "Default")
      (node (ref "C71") (pin "2") (pinfunction "2_2") (pintype "passive"))
      (node (ref "R41") (pin "2") (pinfunction "2_2") (pintype "passive"))
    )
    (net (code "23") (name "VRTC_IO") (class "Default")
      (node (ref "C84") (pin "2") (pinfunction "2_2") (pintype "passive"))
    )
  )
)
